# 172x320_Screen.net
KiCad netlist of a schematic drawn in EAGLE
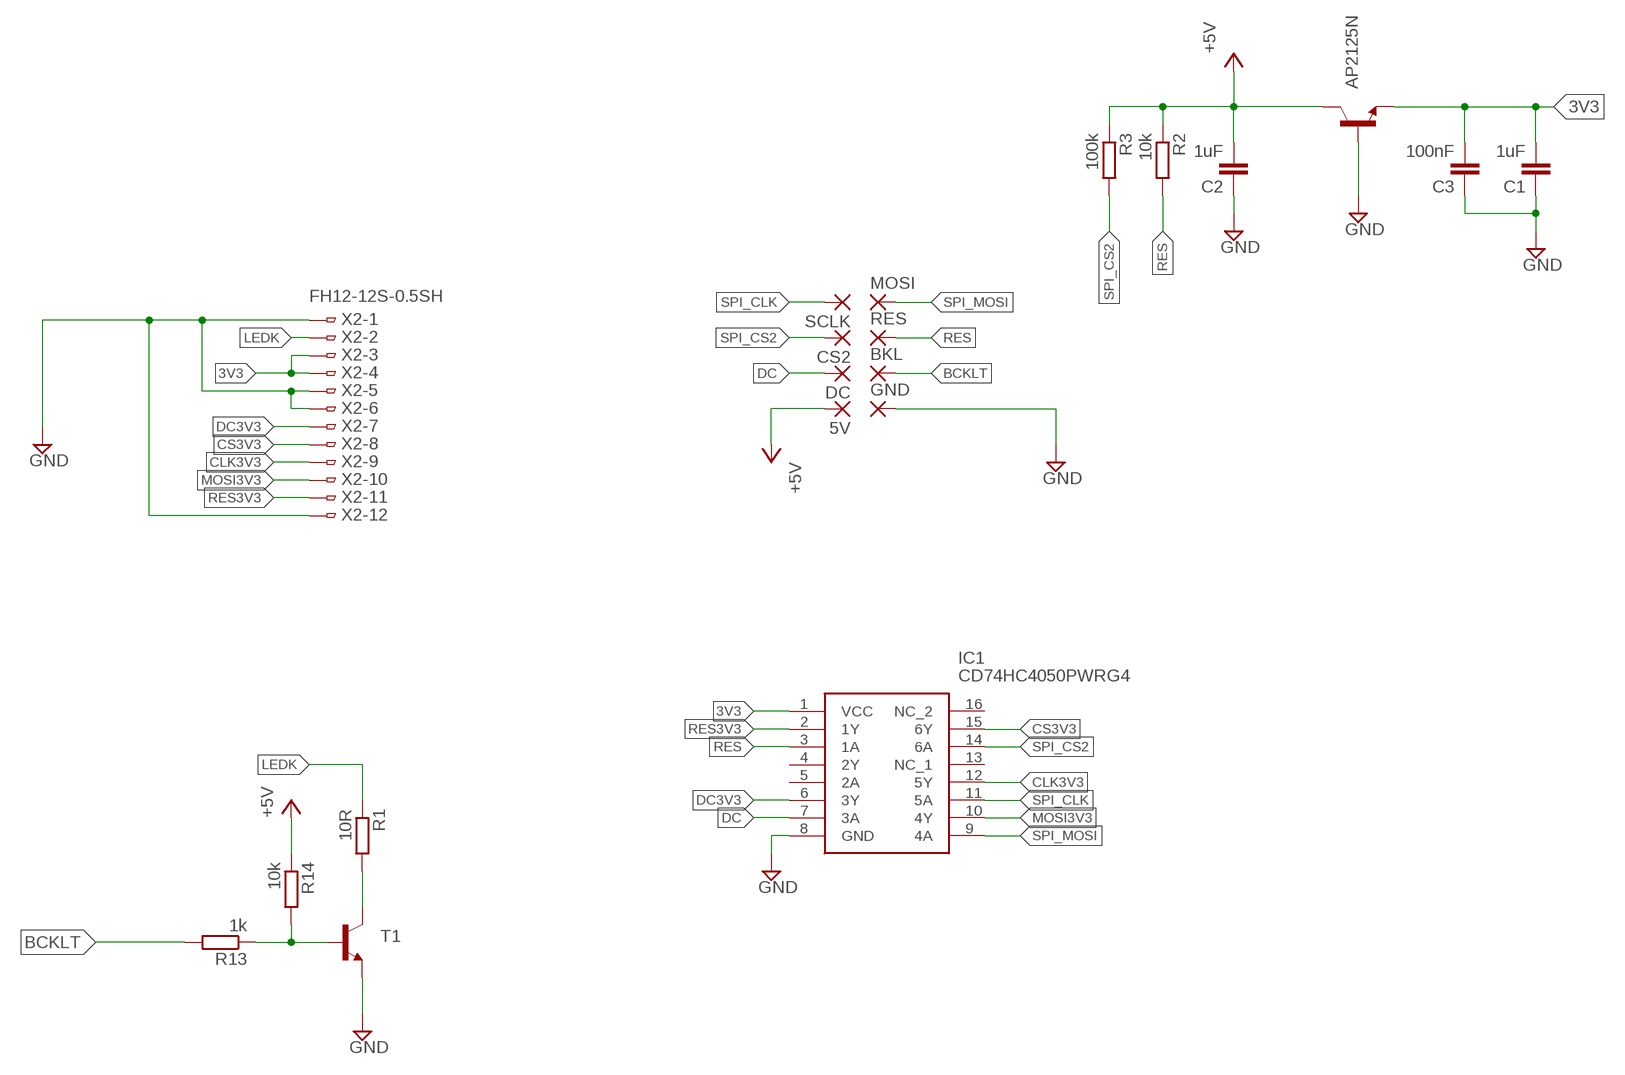
[diagram p0: schematic, sheet 1]

(export (version "E")
  (design (tool "Eeschema 10.0.6"))
  (components
    (comp (ref "5V")
      (value "1,6/0,9")
      (footprint "eagle-import:1,6_0,9")
      (libsource (lib "eagle-import") (part "1,6/0,9"))
    )
    (comp (ref "AP2125N")
      (value "BC817-16-NPN-SOT23-BEC")
      (footprint "eagle-import:SOT23-BEC")
      (libsource (lib "eagle-import") (part "-NPN-SOT23-BECBC817-16"))
    )
    (comp (ref "BKL")
      (value "1,6/0,9")
      (footprint "eagle-import:1,6_0,9")
      (libsource (lib "eagle-import") (part "1,6/0,9"))
    )
    (comp (ref "C1")
      (value "1uF")
      (footprint "eagle-import:C0805")
      (libsource (lib "eagle-import") (part "C-EUC0805"))
    )
    (comp (ref "C2")
      (value "1uF")
      (footprint "eagle-import:C0805")
      (libsource (lib "eagle-import") (part "C-EUC0805"))
    )
    (comp (ref "C3")
      (value "100nF")
      (footprint "eagle-import:C0805")
      (libsource (lib "eagle-import") (part "C-EUC0805"))
    )
    (comp (ref "CS2")
      (value "1,6/0,9")
      (footprint "eagle-import:1,6_0,9")
      (libsource (lib "eagle-import") (part "1,6/0,9"))
    )
    (comp (ref "DC")
      (value "1,6/0,9")
      (footprint "eagle-import:1,6_0,9")
      (libsource (lib "eagle-import") (part "1,6/0,9"))
    )
    (comp (ref "GND")
      (value "1,6/0,9")
      (footprint "eagle-import:1,6_0,9")
      (libsource (lib "eagle-import") (part "1,6/0,9"))
    )
    (comp (ref "IC1")
      (value "CD74HC4050PWRG4")
      (footprint "eagle-import:SOP65P640X120-16N")
      (fields (field (name "MOUSER_PART_NUMBER") "595-CD74HC4050PWRG4"))
      (libsource (lib "eagle-import") (part "CD74HC4050PWRG4"))
    )
    (comp (ref "MOSI")
      (value "1,6/0,9")
      (footprint "eagle-import:1,6_0,9")
      (libsource (lib "eagle-import") (part "1,6/0,9"))
    )
    (comp (ref "R1")
      (value "10R")
      (footprint "eagle-import:R0805")
      (libsource (lib "eagle-import") (part "R-EU_R0805"))
    )
    (comp (ref "R2")
      (value "10k")
      (footprint "eagle-import:R0805")
      (libsource (lib "eagle-import") (part "R-EU_R0805"))
    )
    (comp (ref "R3")
      (value "100k")
      (footprint "eagle-import:R0805")
      (libsource (lib "eagle-import") (part "R-EU_R0805"))
    )
    (comp (ref "R13")
      (value "1k")
      (footprint "eagle-import:R0805")
      (libsource (lib "eagle-import") (part "R-EU_R0805"))
    )
    (comp (ref "R14")
      (value "10k")
      (footprint "eagle-import:R0805")
      (libsource (lib "eagle-import") (part "R-EU_R0805"))
    )
    (comp (ref "RES")
      (value "1,6/0,9")
      (footprint "eagle-import:1,6_0,9")
      (libsource (lib "eagle-import") (part "1,6/0,9"))
    )
    (comp (ref "SCLK")
      (value "1,6/0,9")
      (footprint "eagle-import:1,6_0,9")
      (libsource (lib "eagle-import") (part "1,6/0,9"))
    )
    (comp (ref "T1")
      (value "BC817-16-NPN-SOT23-BEC")
      (footprint "eagle-import:SOT23-BEC")
      (libsource (lib "eagle-import") (part "-NPN-SOT23-BECBC817-16"))
    )
    (comp (ref "X2")
      (value "FH12-12S-0.5SH")
      (footprint "eagle-import:FH12-12S-0.5SH")
      (fields (field (name "MPN") "FH12-12S-0.5SH(55)"))
      (libsource (lib "eagle-import") (part "FH12-12S-0.5SH"))
    )
  )
  (nets
    (net (code "1") (name "+5V") (class "Default")
      (node (ref "5V") (pin "1") (pinfunction "P_1") (pintype "passive"))
      (node (ref "AP2125N") (pin "C") (pinfunction "C_C") (pintype "passive"))
      (node (ref "C2") (pin "2") (pinfunction "2_2") (pintype "passive"))
      (node (ref "R14") (pin "1") (pinfunction "1_1") (pintype "passive"))
      (node (ref "R2") (pin "1") (pinfunction "1_1") (pintype "passive"))
      (node (ref "R3") (pin "1") (pinfunction "1_1") (pintype "passive"))
    )
    (net (code "2") (name "3V3") (class "Default")
      (node (ref "AP2125N") (pin "E") (pinfunction "E_E") (pintype "passive"))
      (node (ref "C1") (pin "2") (pinfunction "2_2") (pintype "passive"))
      (node (ref "C3") (pin "2") (pinfunction "2_2") (pintype "passive"))
      (node (ref "IC1") (pin "1") (pinfunction "VCC_1") (pintype "bidirectional"))
      (node (ref "X2") (pin "3") (pinfunction "1_3") (pintype "passive"))
      (node (ref "X2") (pin "4") (pinfunction "1_4") (pintype "passive"))
    )
    (net (code "3") (name "BCKLT") (class "Default")
      (node (ref "BKL") (pin "1") (pinfunction "P_1") (pintype "passive"))
      (node (ref "R13") (pin "2") (pinfunction "2_2") (pintype "passive"))
    )
    (net (code "4") (name "CLK3V3") (class "Default")
      (node (ref "IC1") (pin "12") (pinfunction "5Y_12") (pintype "bidirectional"))
      (node (ref "X2") (pin "9") (pinfunction "1_9") (pintype "passive"))
    )
    (net (code "5") (name "CS3V3") (class "Default")
      (node (ref "IC1") (pin "15") (pinfunction "6Y_15") (pintype "bidirectional"))
      (node (ref "X2") (pin "8") (pinfunction "1_8") (pintype "passive"))
    )
    (net (code "6") (name "DC") (class "Default")
      (node (ref "DC") (pin "1") (pinfunction "P_1") (pintype "passive"))
      (node (ref "IC1") (pin "7") (pinfunction "3A_7") (pintype "bidirectional"))
    )
    (net (code "7") (name "DC3V3") (class "Default")
      (node (ref "IC1") (pin "6") (pinfunction "3Y_6") (pintype "bidirectional"))
      (node (ref "X2") (pin "7") (pinfunction "1_7") (pintype "passive"))
    )
    (net (code "8") (name "GND") (class "Default")
      (node (ref "AP2125N") (pin "B") (pinfunction "B_B") (pintype "passive"))
      (node (ref "C1") (pin "1") (pinfunction "1_1") (pintype "passive"))
      (node (ref "C2") (pin "1") (pinfunction "1_1") (pintype "passive"))
      (node (ref "C3") (pin "1") (pinfunction "1_1") (pintype "passive"))
      (node (ref "GND") (pin "1") (pinfunction "P_1") (pintype "passive"))
      (node (ref "IC1") (pin "8") (pinfunction "GND_8") (pintype "bidirectional"))
      (node (ref "T1") (pin "E") (pinfunction "E_E") (pintype "passive"))
      (node (ref "X2") (pin "1") (pinfunction "1_1") (pintype "passive"))
      (node (ref "X2") (pin "12") (pinfunction "1_12") (pintype "passive"))
      (node (ref "X2") (pin "5") (pinfunction "1_5") (pintype "passive"))
      (node (ref "X2") (pin "6") (pinfunction "1_6") (pintype "passive"))
    )
    (net (code "9") (name "LEDK") (class "Default")
      (node (ref "R1") (pin "1") (pinfunction "1_1") (pintype "passive"))
      (node (ref "X2") (pin "2") (pinfunction "1_2") (pintype "passive"))
    )
    (net (code "10") (name "MOSI3V3") (class "Default")
      (node (ref "IC1") (pin "10") (pinfunction "4Y_10") (pintype "bidirectional"))
      (node (ref "X2") (pin "10") (pinfunction "1_10") (pintype "passive"))
    )
    (net (code "11") (name "Net-(R1-Pad2)") (class "Default")
      (node (ref "R1") (pin "2") (pinfunction "2_2") (pintype "passive"))
      (node (ref "T1") (pin "C") (pinfunction "C_C") (pintype "passive"))
    )
    (net (code "12") (name "Net-(R13-Pad1)") (class "Default")
      (node (ref "R13") (pin "1") (pinfunction "1_1") (pintype "passive"))
      (node (ref "R14") (pin "2") (pinfunction "2_2") (pintype "passive"))
      (node (ref "T1") (pin "B") (pinfunction "B_B") (pintype "passive"))
    )
    (net (code "13") (name "RES") (class "Default")
      (node (ref "IC1") (pin "3") (pinfunction "1A_3") (pintype "bidirectional"))
      (node (ref "R2") (pin "2") (pinfunction "2_2") (pintype "passive"))
      (node (ref "RES") (pin "1") (pinfunction "P_1") (pintype "passive"))
    )
    (net (code "14") (name "RES3V3") (class "Default")
      (node (ref "IC1") (pin "2") (pinfunction "1Y_2") (pintype "bidirectional"))
      (node (ref "X2") (pin "11") (pinfunction "1_11") (pintype "passive"))
    )
    (net (code "15") (name "SPI_CLK") (class "Default")
      (node (ref "IC1") (pin "11") (pinfunction "5A_11") (pintype "bidirectional"))
      (node (ref "SCLK") (pin "1") (pinfunction "P_1") (pintype "passive"))
    )
    (net (code "16") (name "SPI_CS2") (class "Default")
      (node (ref "CS2") (pin "1") (pinfunction "P_1") (pintype "passive"))
      (node (ref "IC1") (pin "14") (pinfunction "6A_14") (pintype "bidirectional"))
      (node (ref "R3") (pin "2") (pinfunction "2_2") (pintype "passive"))
    )
    (net (code "17") (name "SPI_MOSI") (class "Default")
      (node (ref "IC1") (pin "9") (pinfunction "4A_9") (pintype "bidirectional"))
      (node (ref "MOSI") (pin "1") (pinfunction "P_1") (pintype "passive"))
    )
    (net (code "18") (name "unconnected-(IC1-2A-Pad5)") (class "Default")
      (node (ref "IC1") (pin "5") (pinfunction "2A_5") (pintype "bidirectional"))
    )
    (net (code "19") (name "unconnected-(IC1-2Y-Pad4)") (class "Default")
      (node (ref "IC1") (pin "4") (pinfunction "2Y_4") (pintype "bidirectional"))
    )
    (net (code "20") (name "unconnected-(IC1-NC_1-Pad13)") (class "Default")
      (node (ref "IC1") (pin "13") (pinfunction "NC_1_13") (pintype "bidirectional"))
    )
    (net (code "21") (name "unconnected-(IC1-NC_2-Pad16)") (class "Default")
      (node (ref "IC1") (pin "16") (pinfunction "NC_2_16") (pintype "bidirectional"))
    )
  )
)
